# 2_RKSTM32_MCU.net
KiCad netlist of a schematic drawn in Altium Designer
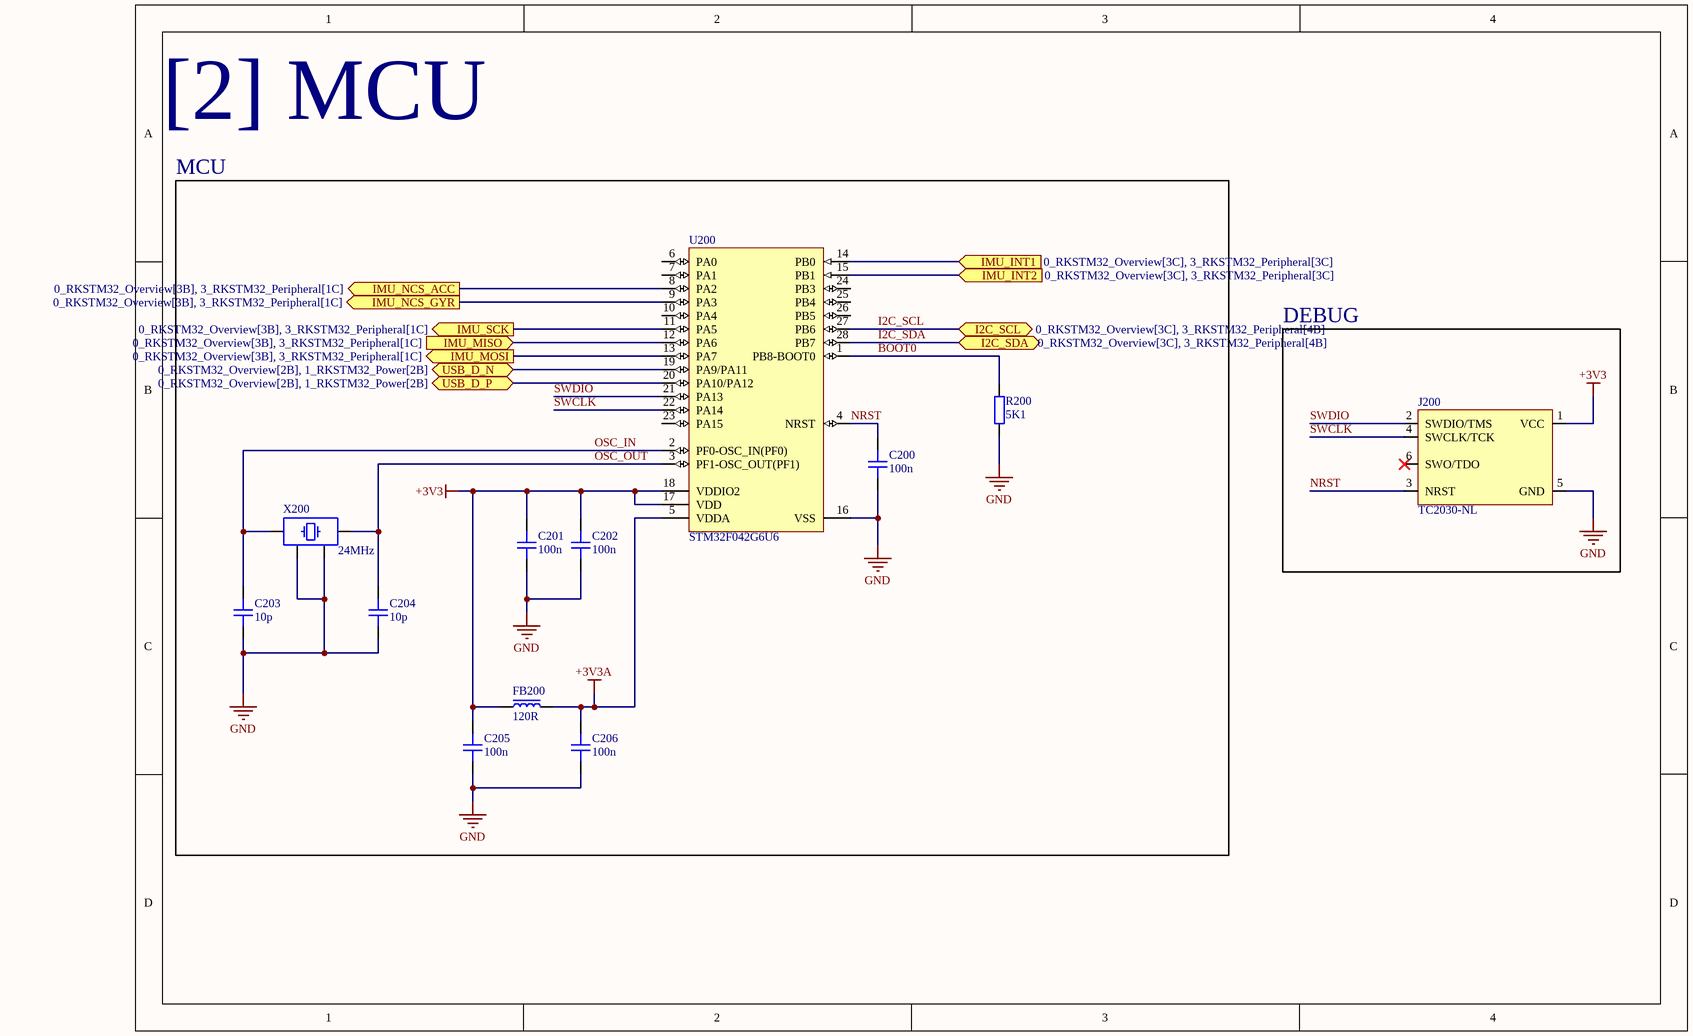
[diagram p0: 2_RKSTM32_MCU.SchDoc]

(export (version "E")
  (design (tool "Eeschema 10.0.6"))
  (components
    (comp (ref "C200")
      (value "100n")
      (footprint "CAP_0805")
      (description "Capacitor SMD 0805")
      (libsource (lib "Schematic-Lib-PhilsLab") (part "CAP_0805"))
    )
    (comp (ref "C201")
      (value "100n")
      (footprint "CAP_0805")
      (description "Capacitor SMD 0805")
      (libsource (lib "Schematic-Lib-PhilsLab") (part "CAP_0805"))
    )
    (comp (ref "C202")
      (value "100n")
      (footprint "CAP_0805")
      (description "Capacitor SMD 0805")
      (libsource (lib "Schematic-Lib-PhilsLab") (part "CAP_0805"))
    )
    (comp (ref "C203")
      (value "10p")
      (footprint "CAP_0805")
      (description "Capacitor SMD 0805")
      (libsource (lib "Schematic-Lib-PhilsLab") (part "CAP_0805"))
    )
    (comp (ref "C204")
      (value "10p")
      (footprint "CAP_0805")
      (description "Capacitor SMD 0805")
      (libsource (lib "Schematic-Lib-PhilsLab") (part "CAP_0805"))
    )
    (comp (ref "C205")
      (value "100n")
      (footprint "CAP_0805")
      (description "Capacitor SMD 0805")
      (libsource (lib "Schematic-Lib-PhilsLab") (part "CAP_0805"))
    )
    (comp (ref "C206")
      (value "100n")
      (footprint "CAP_0805")
      (description "Capacitor SMD 0805")
      (libsource (lib "Schematic-Lib-PhilsLab") (part "CAP_0805"))
    )
    (comp (ref "FB200")
      (value "120R")
      (footprint "FB_0603")
      (description "Ferrite Bead SMD 0603")
      (libsource (lib "Schematic-Lib-PhilsLab") (part "FB_0603"))
    )
    (comp (ref "J200")
      (value "TC2030-NL")
      (footprint "TC2030-NL-FP")
      (description "Tag-Connect No-Solder SWD Debug Connector (No Legs) DO NOT PLACE")
      (fields
        (field (name "MANUFACTURER") "Tag-Connect")
        (field (name "MANUFACTURER PART NUMBER") "TC2030-NL-FP")
      )
      (libsource (lib "Schematic-Lib-PhilsLab") (part "TC2030-NL"))
    )
    (comp (ref "R200")
      (value "5K1")
      (footprint "RES_0603")
      (description "Resistor SMD 0603")
      (libsource (lib "Schematic-Lib-PhilsLab") (part "RES_0603"))
    )
    (comp (ref "U200")
      (value "STM32F042G6U6")
      (footprint "STM-UFQFPN28_V")
      (fields (field (name "MANUFACTURER") "STMicroelectronics"))
      (libsource (lib "Altium Content Vault") (part "MC-ARM-STM32F042-UFQFPN28"))
    )
    (comp (ref "X200")
      (value "24MHz")
      (footprint "XTAL_3225")
      (description "Crystal SMD 24MHz 10PPM 7pF 3225")
      (fields
        (field (name "MANUFACTURER") "Epson")
        (field (name "MANUFACTURER PART NUMBER") "TSX-3225 24.0000MF15X-AC")
      )
      (libsource (lib "Schematic-Lib-PhilsLab") (part "TSX-3225_24.0000MF15X-AC"))
    )
  )
  (nets
    (net (code "1") (name "+3V3") (class "Default")
      (node (ref "C201") (pin "2") (pinfunction "2_2") (pintype "passive"))
      (node (ref "C202") (pin "2") (pinfunction "2_2") (pintype "passive"))
      (node (ref "C205") (pin "2") (pinfunction "2_2") (pintype "passive"))
      (node (ref "FB200") (pin "1") (pinfunction "1_1") (pintype "passive"))
      (node (ref "J200") (pin "1") (pinfunction "VCC_1") (pintype "passive"))
      (node (ref "U200") (pin "17") (pinfunction "VDD_17") (pintype "power_in"))
      (node (ref "U200") (pin "18") (pinfunction "VDDIO2_18") (pintype "power_in"))
    )
    (net (code "2") (name "+3V3A") (class "Default")
      (node (ref "C206") (pin "2") (pinfunction "2_2") (pintype "passive"))
      (node (ref "FB200") (pin "2") (pinfunction "2_2") (pintype "passive"))
      (node (ref "U200") (pin "5") (pinfunction "VDDA_5") (pintype "power_in"))
    )
    (net (code "3") (name "/BOOT0") (class "Default")
      (node (ref "R200") (pin "2") (pinfunction "2_2") (pintype "passive"))
      (node (ref "U200") (pin "1") (pinfunction "PB8-BOOT0_1") (pintype "bidirectional"))
    )
    (net (code "4") (name "/I2C_SCL") (class "Default")
      (node (ref "U200") (pin "27") (pinfunction "PB6_27") (pintype "bidirectional"))
    )
    (net (code "5") (name "/I2C_SDA") (class "Default")
      (node (ref "U200") (pin "28") (pinfunction "PB7_28") (pintype "bidirectional"))
    )
    (net (code "6") (name "/IMU_INT1") (class "Default")
      (node (ref "U200") (pin "14") (pinfunction "PB0_14") (pintype "input"))
    )
    (net (code "7") (name "/IMU_INT2") (class "Default")
      (node (ref "U200") (pin "15") (pinfunction "PB1_15") (pintype "input"))
    )
    (net (code "8") (name "/IMU_MISO") (class "Default")
      (node (ref "U200") (pin "12") (pinfunction "PA6_12") (pintype "bidirectional"))
    )
    (net (code "9") (name "/IMU_MOSI") (class "Default")
      (node (ref "U200") (pin "13") (pinfunction "PA7_13") (pintype "bidirectional"))
    )
    (net (code "10") (name "/IMU_NCS_ACC") (class "Default")
      (node (ref "U200") (pin "8") (pinfunction "PA2_8") (pintype "bidirectional"))
    )
    (net (code "11") (name "/IMU_NCS_GYR") (class "Default")
      (node (ref "U200") (pin "9") (pinfunction "PA3_9") (pintype "bidirectional"))
    )
    (net (code "12") (name "/IMU_SCK") (class "Default")
      (node (ref "U200") (pin "11") (pinfunction "PA5_11") (pintype "bidirectional"))
    )
    (net (code "13") (name "/NRST") (class "Default")
      (node (ref "C200") (pin "2") (pinfunction "2_2") (pintype "passive"))
      (node (ref "J200") (pin "3") (pinfunction "NRST_3") (pintype "passive"))
      (node (ref "U200") (pin "4") (pinfunction "NRST_4") (pintype "bidirectional"))
    )
    (net (code "14") (name "/OSC_IN") (class "Default")
      (node (ref "C203") (pin "2") (pinfunction "2_2") (pintype "passive"))
      (node (ref "U200") (pin "2") (pinfunction "PF0-OSC_IN(PF0)_2") (pintype "bidirectional"))
      (node (ref "X200") (pin "1") (pinfunction "1_1") (pintype "passive"))
    )
    (net (code "15") (name "/OSC_OUT") (class "Default")
      (node (ref "C204") (pin "2") (pinfunction "2_2") (pintype "passive"))
      (node (ref "U200") (pin "3") (pinfunction "PF1-OSC_OUT(PF1)_3") (pintype "bidirectional"))
      (node (ref "X200") (pin "3") (pinfunction "3_3") (pintype "passive"))
    )
    (net (code "16") (name "/SWCLK") (class "Default")
      (node (ref "J200") (pin "4") (pinfunction "SWCLK/TCK_4") (pintype "passive"))
      (node (ref "U200") (pin "22") (pinfunction "PA14_22") (pintype "bidirectional"))
    )
    (net (code "17") (name "/SWDIO") (class "Default")
      (node (ref "J200") (pin "2") (pinfunction "SWDIO/TMS_2") (pintype "passive"))
      (node (ref "U200") (pin "21") (pinfunction "PA13_21") (pintype "bidirectional"))
    )
    (net (code "18") (name "/USB_D_N") (class "Default")
      (node (ref "U200") (pin "19") (pinfunction "PA9/PA11_19") (pintype "bidirectional"))
    )
    (net (code "19") (name "/USB_D_P") (class "Default")
      (node (ref "U200") (pin "20") (pinfunction "PA10/PA12_20") (pintype "bidirectional"))
    )
    (net (code "20") (name "GND") (class "Default")
      (node (ref "C200") (pin "1") (pinfunction "1_1") (pintype "passive"))
      (node (ref "C201") (pin "1") (pinfunction "1_1") (pintype "passive"))
      (node (ref "C202") (pin "1") (pinfunction "1_1") (pintype "passive"))
      (node (ref "C203") (pin "1") (pinfunction "1_1") (pintype "passive"))
      (node (ref "C204") (pin "1") (pinfunction "1_1") (pintype "passive"))
      (node (ref "C205") (pin "1") (pinfunction "1_1") (pintype "passive"))
      (node (ref "C206") (pin "1") (pinfunction "1_1") (pintype "passive"))
      (node (ref "J200") (pin "5") (pinfunction "GND_5") (pintype "passive"))
      (node (ref "R200") (pin "1") (pinfunction "1_1") (pintype "passive"))
      (node (ref "U200") (pin "16") (pinfunction "VSS_16") (pintype "power_in"))
      (node (ref "X200") (pin "2") (pinfunction "2_2") (pintype "passive"))
      (node (ref "X200") (pin "4") (pinfunction "4_4") (pintype "passive"))
    )
    (net (code "21") (name "unconnected-(J200-SWO{slash}TDO-Pad6)") (class "Default")
      (node (ref "J200") (pin "6") (pinfunction "SWO/TDO_6") (pintype "passive+no_connect"))
    )
    (net (code "22") (name "unconnected-(U200-PA0-Pad6)") (class "Default")
      (node (ref "U200") (pin "6") (pinfunction "PA0_6") (pintype "bidirectional"))
    )
    (net (code "23") (name "unconnected-(U200-PA1-Pad7)") (class "Default")
      (node (ref "U200") (pin "7") (pinfunction "PA1_7") (pintype "bidirectional"))
    )
    (net (code "24") (name "unconnected-(U200-PA4-Pad10)") (class "Default")
      (node (ref "U200") (pin "10") (pinfunction "PA4_10") (pintype "bidirectional"))
    )
    (net (code "25") (name "unconnected-(U200-PA15-Pad23)") (class "Default")
      (node (ref "U200") (pin "23") (pinfunction "PA15_23") (pintype "bidirectional"))
    )
    (net (code "26") (name "unconnected-(U200-PB3-Pad24)") (class "Default")
      (node (ref "U200") (pin "24") (pinfunction "PB3_24") (pintype "bidirectional"))
    )
    (net (code "27") (name "unconnected-(U200-PB4-Pad25)") (class "Default")
      (node (ref "U200") (pin "25") (pinfunction "PB4_25") (pintype "bidirectional"))
    )
    (net (code "28") (name "unconnected-(U200-PB5-Pad26)") (class "Default")
      (node (ref "U200") (pin "26") (pinfunction "PB5_26") (pintype "bidirectional"))
    )
  )
)
